# rcio_v1.net
KiCad netlist of a schematic drawn in EAGLE
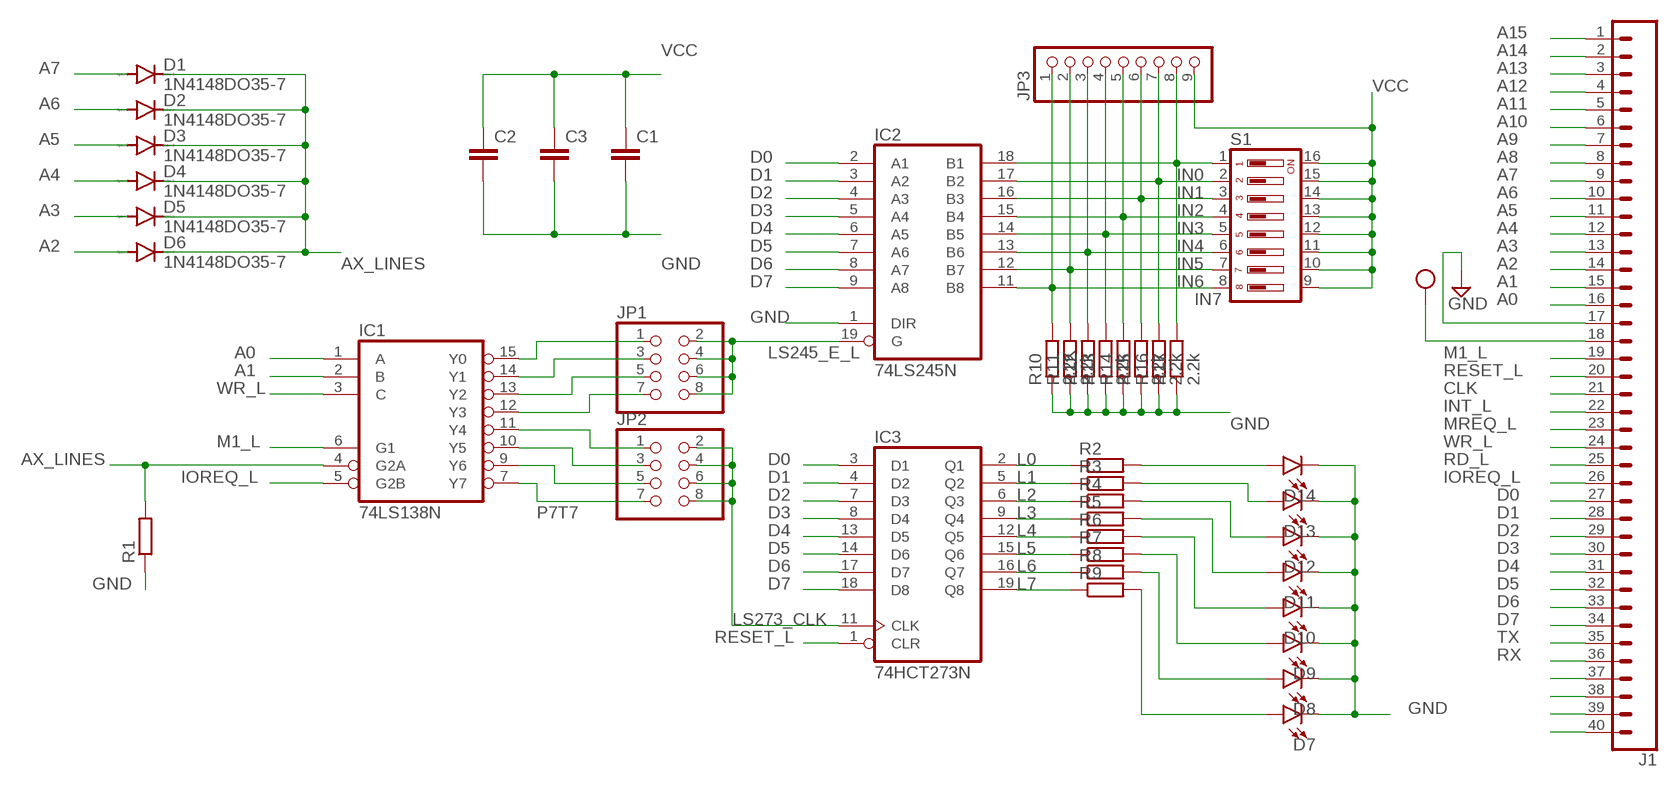
[diagram p0: schematic, sheet 1]

(export (version "E")
  (design (tool "Eeschema 10.0.6"))
  (components
    (comp (ref "C1")
      (value "C-EU050-025X075")
      (footprint "eagle-import:C050-025X075")
      (libsource (lib "eagle-import") (part "rcl_334_C-EU050-025X075"))
    )
    (comp (ref "C2")
      (value "C-EU050-025X075")
      (footprint "eagle-import:C050-025X075")
      (libsource (lib "eagle-import") (part "C-EU050-025X075"))
    )
    (comp (ref "C3")
      (value "C-EU050-025X075")
      (footprint "eagle-import:C050-025X075")
      (libsource (lib "eagle-import") (part "C-EU050-025X075"))
    )
    (comp (ref "D1")
      (value "1N4148DO35-7")
      (footprint "eagle-import:DO35-7")
      (libsource (lib "eagle-import") (part "1N4148DO35-7"))
    )
    (comp (ref "D2")
      (value "1N4148DO35-7")
      (footprint "eagle-import:DO35-7")
      (libsource (lib "eagle-import") (part "1N4148DO35-7"))
    )
    (comp (ref "D3")
      (value "1N4148DO35-7")
      (footprint "eagle-import:DO35-7")
      (libsource (lib "eagle-import") (part "1N4148DO35-7"))
    )
    (comp (ref "D4")
      (value "1N4148DO35-7")
      (footprint "eagle-import:DO35-7")
      (libsource (lib "eagle-import") (part "1N4148DO35-7"))
    )
    (comp (ref "D5")
      (value "1N4148DO35-7")
      (footprint "eagle-import:DO35-7")
      (libsource (lib "eagle-import") (part "1N4148DO35-7"))
    )
    (comp (ref "D6")
      (value "1N4148DO35-7")
      (footprint "eagle-import:DO35-7")
      (libsource (lib "eagle-import") (part "1N4148DO35-7"))
    )
    (comp (ref "D7")
      (value "LED3MM")
      (footprint "eagle-import:LED_3MM")
      (libsource (lib "eagle-import") (part "LED3MM"))
    )
    (comp (ref "D8")
      (value "LED3MM")
      (footprint "eagle-import:LED_3MM")
      (libsource (lib "eagle-import") (part "LED3MM"))
    )
    (comp (ref "D9")
      (value "LED3MM")
      (footprint "eagle-import:LED_3MM")
      (libsource (lib "eagle-import") (part "LED3MM"))
    )
    (comp (ref "D10")
      (value "LED3MM")
      (footprint "eagle-import:LED_3MM")
      (libsource (lib "eagle-import") (part "LED3MM"))
    )
    (comp (ref "D11")
      (value "LED3MM")
      (footprint "eagle-import:LED_3MM")
      (libsource (lib "eagle-import") (part "LED3MM"))
    )
    (comp (ref "D12")
      (value "LED3MM")
      (footprint "eagle-import:LED_3MM")
      (libsource (lib "eagle-import") (part "LED3MM"))
    )
    (comp (ref "D13")
      (value "LED3MM")
      (footprint "eagle-import:LED_3MM")
      (libsource (lib "eagle-import") (part "LED3MM"))
    )
    (comp (ref "D14")
      (value "LED3MM")
      (footprint "eagle-import:LED_3MM")
      (libsource (lib "eagle-import") (part "LED3MM"))
    )
    (comp (ref "IC1")
      (value "74LS138N")
      (footprint "eagle-import:DIL16")
      (libsource (lib "eagle-import") (part "74138NLS"))
    )
    (comp (ref "IC2")
      (value "74LS245N")
      (footprint "eagle-import:DIL20")
      (libsource (lib "eagle-import") (part "74245NLS"))
    )
    (comp (ref "IC3")
      (value "74HCT273N")
      (footprint "eagle-import:DIL20")
      (libsource (lib "eagle-import") (part "74273NHCT"))
    )
    (comp (ref "J1")
      (value "CONN_40OFFSET")
      (footprint "eagle-import:1X40_OFFSET")
      (libsource (lib "eagle-import") (part "CONN_40OFFSET"))
    )
    (comp (ref "JP1")
      (value "PINHD-2X4")
      (footprint "eagle-import:2X04")
      (libsource (lib "eagle-import") (part "PINHD-2X4"))
    )
    (comp (ref "JP2")
      (value "PINHD-2X4")
      (footprint "eagle-import:2X04")
      (libsource (lib "eagle-import") (part "PINHD-2X4"))
    )
    (comp (ref "JP3")
      (value "PINHD-1X9")
      (footprint "eagle-import:1X09")
      (libsource (lib "eagle-import") (part "PINHD-1X9"))
    )
    (comp (ref "R1")
      (value "R-EU_0204/7")
      (footprint "eagle-import:0204_7")
      (libsource (lib "eagle-import") (part "R-EU_0204/7"))
    )
    (comp (ref "R2")
      (value "R-EU_0204/7")
      (footprint "eagle-import:0204_7")
      (libsource (lib "eagle-import") (part "R-EU_0204/7"))
    )
    (comp (ref "R3")
      (value "R-EU_0204/7")
      (footprint "eagle-import:0204_7")
      (libsource (lib "eagle-import") (part "R-EU_0204/7"))
    )
    (comp (ref "R4")
      (value "R-EU_0204/7")
      (footprint "eagle-import:0204_7")
      (libsource (lib "eagle-import") (part "R-EU_0204/7"))
    )
    (comp (ref "R5")
      (value "R-EU_0204/7")
      (footprint "eagle-import:0204_7")
      (libsource (lib "eagle-import") (part "R-EU_0204/7"))
    )
    (comp (ref "R6")
      (value "R-EU_0204/7")
      (footprint "eagle-import:0204_7")
      (libsource (lib "eagle-import") (part "R-EU_0204/7"))
    )
    (comp (ref "R7")
      (value "R-EU_0204/7")
      (footprint "eagle-import:0204_7")
      (libsource (lib "eagle-import") (part "R-EU_0204/7"))
    )
    (comp (ref "R8")
      (value "R-EU_0204/7")
      (footprint "eagle-import:0204_7")
      (libsource (lib "eagle-import") (part "R-EU_0204/7"))
    )
    (comp (ref "R9")
      (value "R-EU_0204/7")
      (footprint "eagle-import:0204_7")
      (libsource (lib "eagle-import") (part "R-EU_0204/7"))
    )
    (comp (ref "R10")
      (value "2.2K")
      (footprint "eagle-import:0204_7")
      (libsource (lib "eagle-import") (part "R-EU_0204/7"))
    )
    (comp (ref "R11")
      (value "2.2k")
      (footprint "eagle-import:0204_7")
      (libsource (lib "eagle-import") (part "R-EU_0204/7"))
    )
    (comp (ref "R12")
      (value "R-EU_0204/7")
      (footprint "eagle-import:0204_7")
      (libsource (lib "eagle-import") (part "R-EU_0204/7"))
    )
    (comp (ref "R13")
      (value "2.2k")
      (footprint "eagle-import:0204_7")
      (libsource (lib "eagle-import") (part "R-EU_0204/7"))
    )
    (comp (ref "R14")
      (value "R-EU_0204/7")
      (footprint "eagle-import:0204_7")
      (libsource (lib "eagle-import") (part "R-EU_0204/7"))
    )
    (comp (ref "R15")
      (value "2.2k")
      (footprint "eagle-import:0204_7")
      (libsource (lib "eagle-import") (part "R-EU_0204/7"))
    )
    (comp (ref "R16")
      (value "2.2k")
      (footprint "eagle-import:0204_7")
      (libsource (lib "eagle-import") (part "R-EU_0204/7"))
    )
    (comp (ref "R17")
      (value "2.2k")
      (footprint "eagle-import:0204_7")
      (libsource (lib "eagle-import") (part "R-EU_0204/7"))
    )
    (comp (ref "S1")
      (value "DP08")
      (footprint "eagle-import:DP-08")
      (libsource (lib "eagle-import") (part "DP08"))
    )
  )
  (nets
    (net (code "1") (name "/A0") (class "Default")
      (node (ref "IC1") (pin "1") (pinfunction "A_1") (pintype "input"))
      (node (ref "J1") (pin "16") (pinfunction "16_16") (pintype "passive"))
    )
    (net (code "2") (name "/A1") (class "Default")
      (node (ref "IC1") (pin "2") (pinfunction "B_2") (pintype "input"))
      (node (ref "J1") (pin "15") (pinfunction "15_15") (pintype "passive"))
    )
    (net (code "3") (name "/A2") (class "Default")
      (node (ref "D6") (pin "A") (pinfunction "A_A") (pintype "passive"))
      (node (ref "J1") (pin "14") (pinfunction "14_14") (pintype "passive"))
    )
    (net (code "4") (name "/A3") (class "Default")
      (node (ref "D5") (pin "A") (pinfunction "A_A") (pintype "passive"))
      (node (ref "J1") (pin "13") (pinfunction "13_13") (pintype "passive"))
    )
    (net (code "5") (name "/A4") (class "Default")
      (node (ref "D4") (pin "A") (pinfunction "A_A") (pintype "passive"))
      (node (ref "J1") (pin "12") (pinfunction "12_12") (pintype "passive"))
    )
    (net (code "6") (name "/A5") (class "Default")
      (node (ref "D3") (pin "A") (pinfunction "A_A") (pintype "passive"))
      (node (ref "J1") (pin "11") (pinfunction "11_11") (pintype "passive"))
    )
    (net (code "7") (name "/A6") (class "Default")
      (node (ref "D2") (pin "A") (pinfunction "A_A") (pintype "passive"))
      (node (ref "J1") (pin "10") (pinfunction "10_10") (pintype "passive"))
    )
    (net (code "8") (name "/A7") (class "Default")
      (node (ref "D1") (pin "A") (pinfunction "A_A") (pintype "passive"))
      (node (ref "J1") (pin "9") (pinfunction "9_9") (pintype "passive"))
    )
    (net (code "9") (name "/A8") (class "Default")
      (node (ref "J1") (pin "8") (pinfunction "8_8") (pintype "passive"))
    )
    (net (code "10") (name "/A9") (class "Default")
      (node (ref "J1") (pin "7") (pinfunction "7_7") (pintype "passive"))
    )
    (net (code "11") (name "/A10") (class "Default")
      (node (ref "J1") (pin "6") (pinfunction "6_6") (pintype "passive"))
    )
    (net (code "12") (name "/A11") (class "Default")
      (node (ref "J1") (pin "5") (pinfunction "5_5") (pintype "passive"))
    )
    (net (code "13") (name "/A12") (class "Default")
      (node (ref "J1") (pin "4") (pinfunction "4_4") (pintype "passive"))
    )
    (net (code "14") (name "/A13") (class "Default")
      (node (ref "J1") (pin "3") (pinfunction "3_3") (pintype "passive"))
    )
    (net (code "15") (name "/A14") (class "Default")
      (node (ref "J1") (pin "2") (pinfunction "2_2") (pintype "passive"))
    )
    (net (code "16") (name "/A15") (class "Default")
      (node (ref "J1") (pin "1") (pinfunction "1_1") (pintype "passive"))
    )
    (net (code "17") (name "/AX_LINES") (class "Default")
      (node (ref "D1") (pin "C") (pinfunction "C_C") (pintype "passive"))
      (node (ref "D2") (pin "C") (pinfunction "C_C") (pintype "passive"))
      (node (ref "D3") (pin "C") (pinfunction "C_C") (pintype "passive"))
      (node (ref "D4") (pin "C") (pinfunction "C_C") (pintype "passive"))
      (node (ref "D5") (pin "C") (pinfunction "C_C") (pintype "passive"))
      (node (ref "D6") (pin "C") (pinfunction "C_C") (pintype "passive"))
      (node (ref "IC1") (pin "4") (pinfunction "G2A_4") (pintype "input"))
      (node (ref "R1") (pin "2") (pinfunction "2_2") (pintype "passive"))
    )
    (net (code "18") (name "/CLK") (class "Default")
      (node (ref "J1") (pin "21") (pinfunction "21_21") (pintype "passive"))
    )
    (net (code "19") (name "/D0") (class "Default")
      (node (ref "IC2") (pin "2") (pinfunction "A1_2") (pintype "bidirectional"))
      (node (ref "IC3") (pin "3") (pinfunction "D1_3") (pintype "input"))
      (node (ref "J1") (pin "27") (pinfunction "27_27") (pintype "passive"))
    )
    (net (code "20") (name "/D1") (class "Default")
      (node (ref "IC2") (pin "3") (pinfunction "A2_3") (pintype "bidirectional"))
      (node (ref "IC3") (pin "4") (pinfunction "D2_4") (pintype "input"))
      (node (ref "J1") (pin "28") (pinfunction "28_28") (pintype "passive"))
    )
    (net (code "21") (name "/D2") (class "Default")
      (node (ref "IC2") (pin "4") (pinfunction "A3_4") (pintype "bidirectional"))
      (node (ref "IC3") (pin "7") (pinfunction "D3_7") (pintype "input"))
      (node (ref "J1") (pin "29") (pinfunction "29_29") (pintype "passive"))
    )
    (net (code "22") (name "/D3") (class "Default")
      (node (ref "IC2") (pin "5") (pinfunction "A4_5") (pintype "bidirectional"))
      (node (ref "IC3") (pin "8") (pinfunction "D4_8") (pintype "input"))
      (node (ref "J1") (pin "30") (pinfunction "30_30") (pintype "passive"))
    )
    (net (code "23") (name "/D4") (class "Default")
      (node (ref "IC2") (pin "6") (pinfunction "A5_6") (pintype "bidirectional"))
      (node (ref "IC3") (pin "13") (pinfunction "D5_13") (pintype "input"))
      (node (ref "J1") (pin "31") (pinfunction "31_31") (pintype "passive"))
    )
    (net (code "24") (name "/D5") (class "Default")
      (node (ref "IC2") (pin "7") (pinfunction "A6_7") (pintype "bidirectional"))
      (node (ref "IC3") (pin "14") (pinfunction "D6_14") (pintype "input"))
      (node (ref "J1") (pin "32") (pinfunction "32_32") (pintype "passive"))
    )
    (net (code "25") (name "/D6") (class "Default")
      (node (ref "IC2") (pin "8") (pinfunction "A7_8") (pintype "bidirectional"))
      (node (ref "IC3") (pin "17") (pinfunction "D7_17") (pintype "input"))
      (node (ref "J1") (pin "33") (pinfunction "33_33") (pintype "passive"))
    )
    (net (code "26") (name "/D7") (class "Default")
      (node (ref "IC2") (pin "9") (pinfunction "A8_9") (pintype "bidirectional"))
      (node (ref "IC3") (pin "18") (pinfunction "D8_18") (pintype "input"))
      (node (ref "J1") (pin "34") (pinfunction "34_34") (pintype "passive"))
    )
    (net (code "27") (name "/IN0") (class "Default")
      (node (ref "IC2") (pin "18") (pinfunction "B1_18") (pintype "bidirectional"))
      (node (ref "JP3") (pin "8") (pinfunction "8_8") (pintype "passive"))
      (node (ref "R17") (pin "2") (pinfunction "2_2") (pintype "passive"))
      (node (ref "S1") (pin "1") (pinfunction "1_1") (pintype "passive"))
    )
    (net (code "28") (name "/IN1") (class "Default")
      (node (ref "IC2") (pin "17") (pinfunction "B2_17") (pintype "bidirectional"))
      (node (ref "JP3") (pin "7") (pinfunction "7_7") (pintype "passive"))
      (node (ref "R16") (pin "2") (pinfunction "2_2") (pintype "passive"))
      (node (ref "S1") (pin "2") (pinfunction "2_2") (pintype "passive"))
    )
    (net (code "29") (name "/IN2") (class "Default")
      (node (ref "IC2") (pin "16") (pinfunction "B3_16") (pintype "bidirectional"))
      (node (ref "JP3") (pin "6") (pinfunction "6_6") (pintype "passive"))
      (node (ref "R15") (pin "2") (pinfunction "2_2") (pintype "passive"))
      (node (ref "S1") (pin "3") (pinfunction "3_3") (pintype "passive"))
    )
    (net (code "30") (name "/IN3") (class "Default")
      (node (ref "IC2") (pin "15") (pinfunction "B4_15") (pintype "bidirectional"))
      (node (ref "JP3") (pin "5") (pinfunction "5_5") (pintype "passive"))
      (node (ref "R14") (pin "2") (pinfunction "2_2") (pintype "passive"))
      (node (ref "S1") (pin "4") (pinfunction "4_4") (pintype "passive"))
    )
    (net (code "31") (name "/IN4") (class "Default")
      (node (ref "IC2") (pin "14") (pinfunction "B5_14") (pintype "bidirectional"))
      (node (ref "JP3") (pin "4") (pinfunction "4_4") (pintype "passive"))
      (node (ref "R13") (pin "2") (pinfunction "2_2") (pintype "passive"))
      (node (ref "S1") (pin "5") (pinfunction "5_5") (pintype "passive"))
    )
    (net (code "32") (name "/IN5") (class "Default")
      (node (ref "IC2") (pin "13") (pinfunction "B6_13") (pintype "bidirectional"))
      (node (ref "JP3") (pin "3") (pinfunction "3_3") (pintype "passive"))
      (node (ref "R12") (pin "2") (pinfunction "2_2") (pintype "passive"))
      (node (ref "S1") (pin "6") (pinfunction "6_6") (pintype "passive"))
    )
    (net (code "33") (name "/IN6") (class "Default")
      (node (ref "IC2") (pin "12") (pinfunction "B7_12") (pintype "bidirectional"))
      (node (ref "JP3") (pin "2") (pinfunction "2_2") (pintype "passive"))
      (node (ref "R11") (pin "2") (pinfunction "2_2") (pintype "passive"))
      (node (ref "S1") (pin "7") (pinfunction "7_7") (pintype "passive"))
    )
    (net (code "34") (name "/IN7") (class "Default")
      (node (ref "IC2") (pin "11") (pinfunction "B8_11") (pintype "bidirectional"))
      (node (ref "JP3") (pin "1") (pinfunction "1_1") (pintype "passive"))
      (node (ref "R10") (pin "2") (pinfunction "2_2") (pintype "passive"))
      (node (ref "S1") (pin "8") (pinfunction "8_8") (pintype "passive"))
    )
    (net (code "35") (name "/INT_L") (class "Default")
      (node (ref "J1") (pin "22") (pinfunction "22_22") (pintype "passive"))
    )
    (net (code "36") (name "/IOREQ_L") (class "Default")
      (node (ref "IC1") (pin "5") (pinfunction "G2B_5") (pintype "input"))
      (node (ref "J1") (pin "26") (pinfunction "26_26") (pintype "passive"))
    )
    (net (code "37") (name "/L0") (class "Default")
      (node (ref "IC3") (pin "2") (pinfunction "Q1_2") (pintype "output"))
      (node (ref "R2") (pin "1") (pinfunction "1_1") (pintype "passive"))
    )
    (net (code "38") (name "/L1") (class "Default")
      (node (ref "IC3") (pin "5") (pinfunction "Q2_5") (pintype "output"))
      (node (ref "R3") (pin "1") (pinfunction "1_1") (pintype "passive"))
    )
    (net (code "39") (name "/L2") (class "Default")
      (node (ref "IC3") (pin "6") (pinfunction "Q3_6") (pintype "output"))
      (node (ref "R4") (pin "1") (pinfunction "1_1") (pintype "passive"))
    )
    (net (code "40") (name "/L3") (class "Default")
      (node (ref "IC3") (pin "9") (pinfunction "Q4_9") (pintype "output"))
      (node (ref "R5") (pin "1") (pinfunction "1_1") (pintype "passive"))
    )
    (net (code "41") (name "/L4") (class "Default")
      (node (ref "IC3") (pin "12") (pinfunction "Q5_12") (pintype "output"))
      (node (ref "R6") (pin "1") (pinfunction "1_1") (pintype "passive"))
    )
    (net (code "42") (name "/L5") (class "Default")
      (node (ref "IC3") (pin "15") (pinfunction "Q6_15") (pintype "output"))
      (node (ref "R7") (pin "1") (pinfunction "1_1") (pintype "passive"))
    )
    (net (code "43") (name "/L6") (class "Default")
      (node (ref "IC3") (pin "16") (pinfunction "Q7_16") (pintype "output"))
      (node (ref "R8") (pin "1") (pinfunction "1_1") (pintype "passive"))
    )
    (net (code "44") (name "/L7") (class "Default")
      (node (ref "IC3") (pin "19") (pinfunction "Q8_19") (pintype "output"))
      (node (ref "R9") (pin "1") (pinfunction "1_1") (pintype "passive"))
    )
    (net (code "45") (name "/LS245_E_L") (class "Default")
      (node (ref "IC2") (pin "19") (pinfunction "G_19") (pintype "input"))
      (node (ref "JP1") (pin "2") (pinfunction "2_2") (pintype "passive"))
      (node (ref "JP1") (pin "4") (pinfunction "4_4") (pintype "passive"))
      (node (ref "JP1") (pin "6") (pinfunction "6_6") (pintype "passive"))
      (node (ref "JP1") (pin "8") (pinfunction "8_8") (pintype "passive"))
    )
    (net (code "46") (name "/LS273_CLK") (class "Default")
      (node (ref "IC3") (pin "11") (pinfunction "CLK_11") (pintype "input"))
      (node (ref "JP2") (pin "2") (pinfunction "2_2") (pintype "passive"))
      (node (ref "JP2") (pin "4") (pinfunction "4_4") (pintype "passive"))
      (node (ref "JP2") (pin "6") (pinfunction "6_6") (pintype "passive"))
      (node (ref "JP2") (pin "8") (pinfunction "8_8") (pintype "passive"))
    )
    (net (code "47") (name "/M1_L") (class "Default")
      (node (ref "IC1") (pin "6") (pinfunction "G1_6") (pintype "input"))
      (node (ref "J1") (pin "19") (pinfunction "19_19") (pintype "passive"))
    )
    (net (code "48") (name "/MREQ_L") (class "Default")
      (node (ref "J1") (pin "23") (pinfunction "23_23") (pintype "passive"))
    )
    (net (code "49") (name "/P7T7") (class "Default")
      (node (ref "IC1") (pin "7") (pinfunction "Y7_7") (pintype "output"))
      (node (ref "JP2") (pin "7") (pinfunction "7_7") (pintype "passive"))
    )
    (net (code "50") (name "/RD_L") (class "Default")
      (node (ref "J1") (pin "25") (pinfunction "25_25") (pintype "passive"))
    )
    (net (code "51") (name "/RESET_L") (class "Default")
      (node (ref "IC3") (pin "1") (pinfunction "CLR_1") (pintype "input"))
      (node (ref "J1") (pin "20") (pinfunction "20_20") (pintype "passive"))
    )
    (net (code "52") (name "/RX") (class "Default")
      (node (ref "J1") (pin "36") (pinfunction "36_36") (pintype "passive"))
    )
    (net (code "53") (name "/TX") (class "Default")
      (node (ref "J1") (pin "35") (pinfunction "35_35") (pintype "passive"))
    )
    (net (code "54") (name "/WR_L") (class "Default")
      (node (ref "IC1") (pin "3") (pinfunction "C_3") (pintype "input"))
      (node (ref "J1") (pin "24") (pinfunction "24_24") (pintype "passive"))
    )
    (net (code "55") (name "GND") (class "Default")
      (node (ref "C1") (pin "2") (pinfunction "2_2") (pintype "passive"))
      (node (ref "C2") (pin "2") (pinfunction "2_2") (pintype "passive"))
      (node (ref "C3") (pin "2") (pinfunction "2_2") (pintype "passive"))
      (node (ref "D10") (pin "K") (pinfunction "C_K") (pintype "passive"))
      (node (ref "D11") (pin "K") (pinfunction "C_K") (pintype "passive"))
      (node (ref "D12") (pin "K") (pinfunction "C_K") (pintype "passive"))
      (node (ref "D13") (pin "K") (pinfunction "C_K") (pintype "passive"))
      (node (ref "D14") (pin "K") (pinfunction "C_K") (pintype "passive"))
      (node (ref "D7") (pin "K") (pinfunction "C_K") (pintype "passive"))
      (node (ref "D8") (pin "K") (pinfunction "C_K") (pintype "passive"))
      (node (ref "D9") (pin "K") (pinfunction "C_K") (pintype "passive"))
      (node (ref "IC2") (pin "1") (pinfunction "DIR_1") (pintype "input"))
      (node (ref "J1") (pin "17") (pinfunction "17_17") (pintype "passive"))
      (node (ref "R1") (pin "1") (pinfunction "1_1") (pintype "passive"))
      (node (ref "R10") (pin "1") (pinfunction "1_1") (pintype "passive"))
      (node (ref "R11") (pin "1") (pinfunction "1_1") (pintype "passive"))
      (node (ref "R12") (pin "1") (pinfunction "1_1") (pintype "passive"))
      (node (ref "R13") (pin "1") (pinfunction "1_1") (pintype "passive"))
      (node (ref "R14") (pin "1") (pinfunction "1_1") (pintype "passive"))
      (node (ref "R15") (pin "1") (pinfunction "1_1") (pintype "passive"))
      (node (ref "R16") (pin "1") (pinfunction "1_1") (pintype "passive"))
      (node (ref "R17") (pin "1") (pinfunction "1_1") (pintype "passive"))
    )
    (net (code "56") (name "Net-(D7-PadA)") (class "Default")
      (node (ref "D7") (pin "A") (pinfunction "A_A") (pintype "passive"))
      (node (ref "R9") (pin "2") (pinfunction "2_2") (pintype "passive"))
    )
    (net (code "57") (name "Net-(D8-PadA)") (class "Default")
      (node (ref "D8") (pin "A") (pinfunction "A_A") (pintype "passive"))
      (node (ref "R8") (pin "2") (pinfunction "2_2") (pintype "passive"))
    )
    (net (code "58") (name "Net-(D9-PadA)") (class "Default")
      (node (ref "D9") (pin "A") (pinfunction "A_A") (pintype "passive"))
      (node (ref "R7") (pin "2") (pinfunction "2_2") (pintype "passive"))
    )
    (net (code "59") (name "Net-(D10-PadA)") (class "Default")
      (node (ref "D10") (pin "A") (pinfunction "A_A") (pintype "passive"))
      (node (ref "R6") (pin "2") (pinfunction "2_2") (pintype "passive"))
    )
    (net (code "60") (name "Net-(D11-PadA)") (class "Default")
      (node (ref "D11") (pin "A") (pinfunction "A_A") (pintype "passive"))
      (node (ref "R5") (pin "2") (pinfunction "2_2") (pintype "passive"))
    )
    (net (code "61") (name "Net-(D12-PadA)") (class "Default")
      (node (ref "D12") (pin "A") (pinfunction "A_A") (pintype "passive"))
      (node (ref "R4") (pin "2") (pinfunction "2_2") (pintype "passive"))
    )
    (net (code "62") (name "Net-(D13-PadA)") (class "Default")
      (node (ref "D13") (pin "A") (pinfunction "A_A") (pintype "passive"))
      (node (ref "R3") (pin "2") (pinfunction "2_2") (pintype "passive"))
    )
    (net (code "63") (name "Net-(D14-PadA)") (class "Default")
      (node (ref "D14") (pin "A") (pinfunction "A_A") (pintype "passive"))
      (node (ref "R2") (pin "2") (pinfunction "2_2") (pintype "passive"))
    )
    (net (code "64") (name "Net-(IC1A-Y0)") (class "Default")
      (node (ref "IC1") (pin "15") (pinfunction "Y0_15") (pintype "output"))
      (node (ref "JP1") (pin "1") (pinfunction "1_1") (pintype "passive"))
    )
    (net (code "65") (name "Net-(IC1A-Y1)") (class "Default")
      (node (ref "IC1") (pin "14") (pinfunction "Y1_14") (pintype "output"))
      (node (ref "JP1") (pin "3") (pinfunction "3_3") (pintype "passive"))
    )
    (net (code "66") (name "Net-(IC1A-Y2)") (class "Default")
      (node (ref "IC1") (pin "13") (pinfunction "Y2_13") (pintype "output"))
      (node (ref "JP1") (pin "5") (pinfunction "5_5") (pintype "passive"))
    )
    (net (code "67") (name "Net-(IC1A-Y3)") (class "Default")
      (node (ref "IC1") (pin "12") (pinfunction "Y3_12") (pintype "output"))
      (node (ref "JP1") (pin "7") (pinfunction "7_7") (pintype "passive"))
    )
    (net (code "68") (name "Net-(IC1A-Y4)") (class "Default")
      (node (ref "IC1") (pin "11") (pinfunction "Y4_11") (pintype "output"))
      (node (ref "JP2") (pin "1") (pinfunction "1_1") (pintype "passive"))
    )
    (net (code "69") (name "Net-(IC1A-Y5)") (class "Default")
      (node (ref "IC1") (pin "10") (pinfunction "Y5_10") (pintype "output"))
      (node (ref "JP2") (pin "3") (pinfunction "3_3") (pintype "passive"))
    )
    (net (code "70") (name "Net-(IC1A-Y6)") (class "Default")
      (node (ref "IC1") (pin "9") (pinfunction "Y6_9") (pintype "output"))
      (node (ref "JP2") (pin "5") (pinfunction "5_5") (pintype "passive"))
    )
    (net (code "71") (name "VCC") (class "Default")
      (node (ref "C1") (pin "1") (pinfunction "1_1") (pintype "passive"))
      (node (ref "C2") (pin "1") (pinfunction "1_1") (pintype "passive"))
      (node (ref "C3") (pin "1") (pinfunction "1_1") (pintype "passive"))
      (node (ref "J1") (pin "18") (pinfunction "18_18") (pintype "passive"))
      (node (ref "JP3") (pin "9") (pinfunction "9_9") (pintype "passive"))
      (node (ref "S1") (pin "10") (pinfunction "10_10") (pintype "passive"))
      (node (ref "S1") (pin "11") (pinfunction "11_11") (pintype "passive"))
      (node (ref "S1") (pin "12") (pinfunction "12_12") (pintype "passive"))
      (node (ref "S1") (pin "13") (pinfunction "13_13") (pintype "passive"))
      (node (ref "S1") (pin "14") (pinfunction "14_14") (pintype "passive"))
      (node (ref "S1") (pin "15") (pinfunction "15_15") (pintype "passive"))
      (node (ref "S1") (pin "16") (pinfunction "16_16") (pintype "passive"))
      (node (ref "S1") (pin "9") (pinfunction "9_9") (pintype "passive"))
    )
    (net (code "72") (name "unconnected-(J1-Pad37)") (class "Default")
      (node (ref "J1") (pin "37") (pinfunction "37_37") (pintype "passive"))
    )
    (net (code "73") (name "unconnected-(J1-Pad38)") (class "Default")
      (node (ref "J1") (pin "38") (pinfunction "38_38") (pintype "passive"))
    )
    (net (code "74") (name "unconnected-(J1-Pad39)") (class "Default")
      (node (ref "J1") (pin "39") (pinfunction "39_39") (pintype "passive"))
    )
    (net (code "75") (name "unconnected-(J1-Pad40)") (class "Default")
      (node (ref "J1") (pin "40") (pinfunction "40_40") (pintype "passive"))
    )
  )
)
